# ARE_adaptadora_PIC_8-14pin.net
KiCad netlist of a schematic drawn in EAGLE
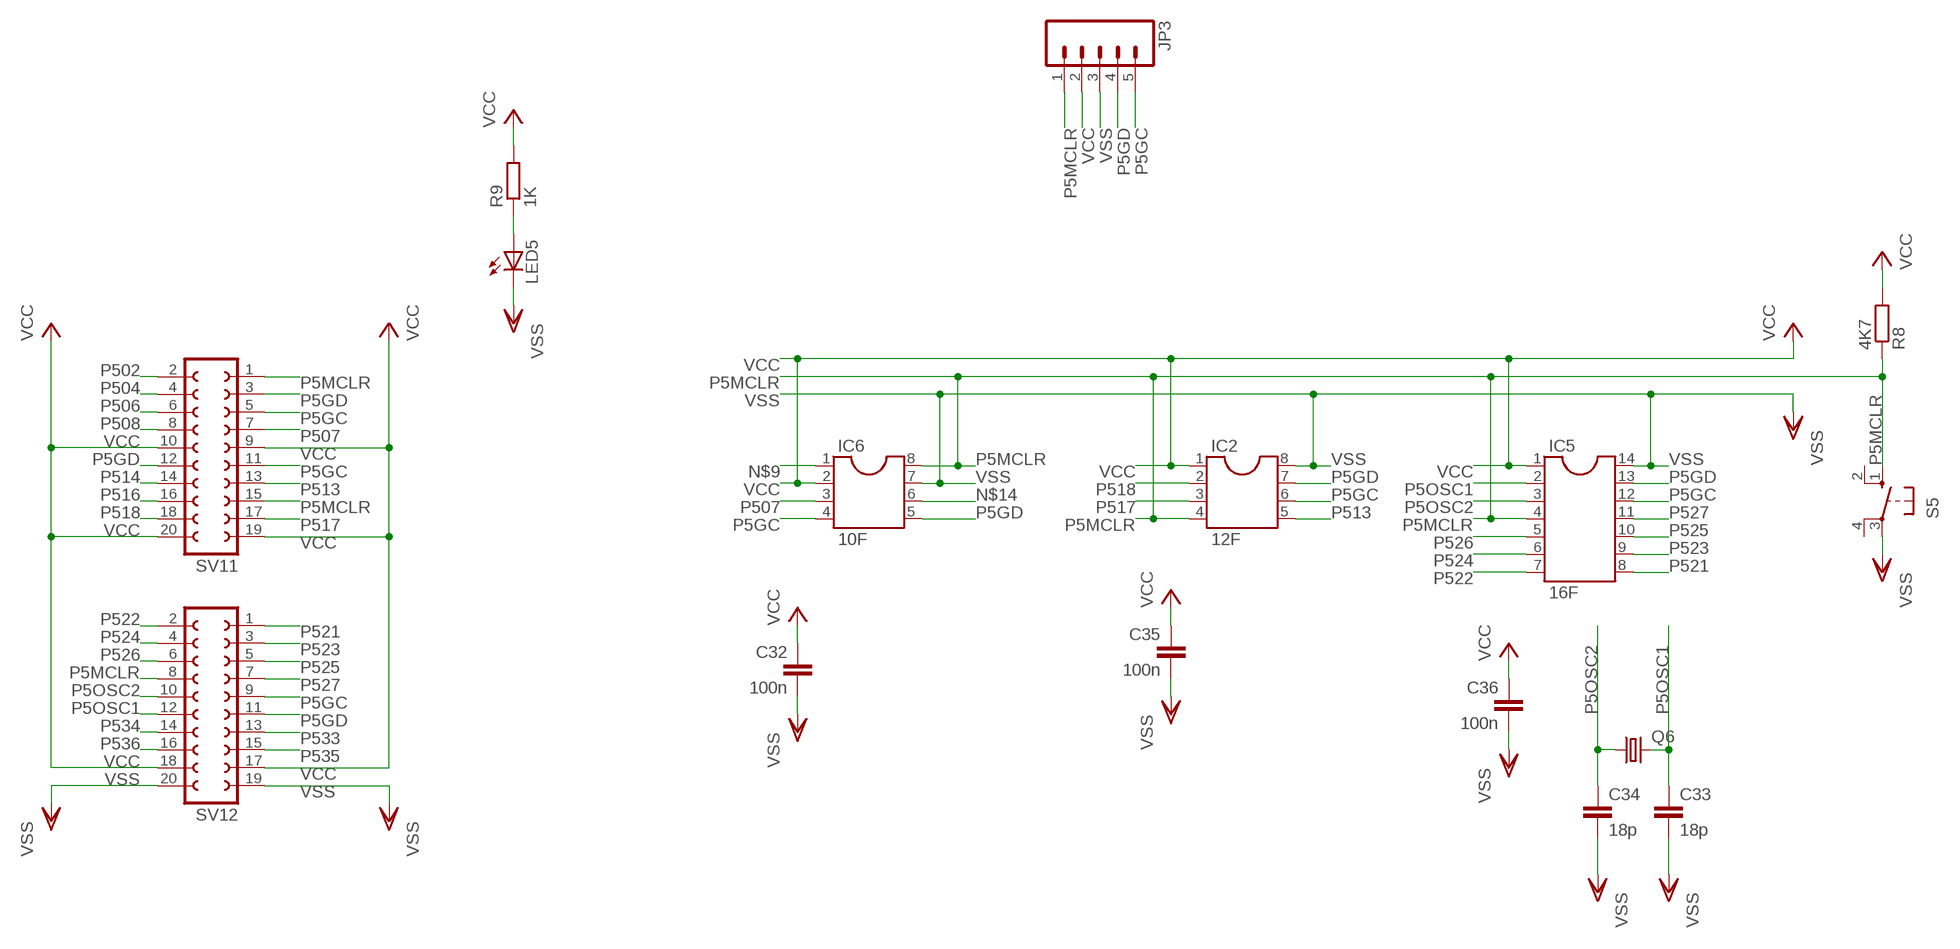
[diagram p0: schematic, sheet 1]

(export (version "E")
  (design (tool "Eeschema 10.0.6"))
  (components
    (comp (ref "C32")
      (value "100n")
      (footprint "eagle-import:C0805")
      (libsource (lib "eagle-import") (part "C-EUC0805"))
    )
    (comp (ref "C33")
      (value "18p")
      (footprint "eagle-import:C0805")
      (libsource (lib "eagle-import") (part "C-EUC0805"))
    )
    (comp (ref "C34")
      (value "18p")
      (footprint "eagle-import:C0805")
      (libsource (lib "eagle-import") (part "C-EUC0805"))
    )
    (comp (ref "C35")
      (value "100n")
      (footprint "eagle-import:C0805")
      (libsource (lib "eagle-import") (part "C-EUC0805"))
    )
    (comp (ref "C36")
      (value "100n")
      (footprint "eagle-import:C0805")
      (libsource (lib "eagle-import") (part "C-EUC0805"))
    )
    (comp (ref "IC2")
      (value "12F")
      (footprint "eagle-import:SOCKET-08")
      (libsource (lib "eagle-import") (part "DIL8S"))
    )
    (comp (ref "IC5")
      (value "16F")
      (footprint "eagle-import:SOCKET-14")
      (libsource (lib "eagle-import") (part "DIL14S"))
    )
    (comp (ref "IC6")
      (value "10F")
      (footprint "eagle-import:SOCKET-08")
      (libsource (lib "eagle-import") (part "DIL8S"))
    )
    (comp (ref "JP3")
      (value "M05PTH")
      (footprint "eagle-import:1X05")
      (libsource (lib "eagle-import") (part "M05PTH"))
    )
    (comp (ref "LED5")
      (value "LEDCHIPLED_0805")
      (footprint "eagle-import:CHIPLED_0805")
      (libsource (lib "eagle-import") (part "LEDCHIPLED_0805"))
    )
    (comp (ref "Q6")
      (value "CRYSTALHC18U-V")
      (footprint "eagle-import:HC18U-V")
      (libsource (lib "eagle-import") (part "CRYSTALHC18U-V"))
    )
    (comp (ref "R8")
      (value "4K7")
      (footprint "eagle-import:R0805")
      (libsource (lib "eagle-import") (part "R-EU_R0805"))
    )
    (comp (ref "R9")
      (value "1K")
      (footprint "eagle-import:R0805")
      (libsource (lib "eagle-import") (part "R-EU_R0805"))
    )
    (comp (ref "S5")
      (value "10-XX")
      (footprint "eagle-import:B3F-10XX")
      (fields
        (field (name "MPN") "B3F-1000")
        (field (name "MPN_1") "B3F-1000")
        (field (name "OC_FARNELL") "176432")
        (field (name "OC_NEWARK") "36M3542")
      )
      (libsource (lib "eagle-import") (part "10-XX"))
    )
    (comp (ref "SV11")
      (value "FE10-2W")
      (footprint "eagle-import:FE10-2W")
      (libsource (lib "eagle-import") (part "FE10-2W"))
    )
    (comp (ref "SV12")
      (value "FE10-2W")
      (footprint "eagle-import:FE10-2W")
      (libsource (lib "eagle-import") (part "FE10-2W"))
    )
  )
  (nets
    (net (code "1") (name "/N$9") (class "Default")
      (node (ref "IC6") (pin "1") (pinfunction "1_1") (pintype "passive"))
    )
    (net (code "2") (name "/N$14") (class "Default")
      (node (ref "IC6") (pin "6") (pinfunction "6_6") (pintype "passive"))
    )
    (net (code "3") (name "/P5GC") (class "Default")
      (node (ref "IC2") (pin "6") (pinfunction "6_6") (pintype "passive"))
      (node (ref "IC5") (pin "12") (pinfunction "12_12") (pintype "passive"))
      (node (ref "IC6") (pin "4") (pinfunction "4_4") (pintype "passive"))
      (node (ref "JP3") (pin "5") (pinfunction "5_5") (pintype "passive"))
      (node (ref "SV11") (pin "11") (pinfunction "11_11") (pintype "passive"))
      (node (ref "SV11") (pin "5") (pinfunction "5_5") (pintype "passive"))
      (node (ref "SV12") (pin "9") (pinfunction "9_9") (pintype "passive"))
    )
    (net (code "4") (name "/P5GD") (class "Default")
      (node (ref "IC2") (pin "7") (pinfunction "7_7") (pintype "passive"))
      (node (ref "IC5") (pin "13") (pinfunction "13_13") (pintype "passive"))
      (node (ref "IC6") (pin "5") (pinfunction "5_5") (pintype "passive"))
      (node (ref "JP3") (pin "4") (pinfunction "4_4") (pintype "passive"))
      (node (ref "SV11") (pin "12") (pinfunction "12_12") (pintype "passive"))
      (node (ref "SV11") (pin "3") (pinfunction "3_3") (pintype "passive"))
      (node (ref "SV12") (pin "11") (pinfunction "11_11") (pintype "passive"))
    )
    (net (code "5") (name "/P5MCLR") (class "Default")
      (node (ref "IC2") (pin "4") (pinfunction "4_4") (pintype "passive"))
      (node (ref "IC5") (pin "4") (pinfunction "4_4") (pintype "passive"))
      (node (ref "IC6") (pin "8") (pinfunction "8_8") (pintype "passive"))
      (node (ref "JP3") (pin "1") (pinfunction "1_1") (pintype "passive"))
      (node (ref "R8") (pin "1") (pinfunction "1_1") (pintype "passive"))
      (node (ref "S5") (pin "1") (pinfunction "S_1") (pintype "passive"))
      (node (ref "SV11") (pin "1") (pinfunction "1_1") (pintype "passive"))
      (node (ref "SV11") (pin "15") (pinfunction "15_15") (pintype "passive"))
      (node (ref "SV12") (pin "8") (pinfunction "8_8") (pintype "passive"))
    )
    (net (code "6") (name "/P5OSC1") (class "Default")
      (node (ref "C33") (pin "1") (pinfunction "1_1") (pintype "passive"))
      (node (ref "IC5") (pin "2") (pinfunction "2_2") (pintype "passive"))
      (node (ref "Q6") (pin "2") (pinfunction "2_2") (pintype "passive"))
      (node (ref "SV12") (pin "12") (pinfunction "12_12") (pintype "passive"))
    )
    (net (code "7") (name "/P5OSC2") (class "Default")
      (node (ref "C34") (pin "1") (pinfunction "1_1") (pintype "passive"))
      (node (ref "IC5") (pin "3") (pinfunction "3_3") (pintype "passive"))
      (node (ref "Q6") (pin "1") (pinfunction "1_1") (pintype "passive"))
      (node (ref "SV12") (pin "10") (pinfunction "10_10") (pintype "passive"))
    )
    (net (code "8") (name "/P502") (class "Default")
      (node (ref "SV11") (pin "2") (pinfunction "2_2") (pintype "passive"))
    )
    (net (code "9") (name "/P504") (class "Default")
      (node (ref "SV11") (pin "4") (pinfunction "4_4") (pintype "passive"))
    )
    (net (code "10") (name "/P506") (class "Default")
      (node (ref "SV11") (pin "6") (pinfunction "6_6") (pintype "passive"))
    )
    (net (code "11") (name "/P507") (class "Default")
      (node (ref "IC6") (pin "3") (pinfunction "3_3") (pintype "passive"))
      (node (ref "SV11") (pin "7") (pinfunction "7_7") (pintype "passive"))
    )
    (net (code "12") (name "/P508") (class "Default")
      (node (ref "SV11") (pin "8") (pinfunction "8_8") (pintype "passive"))
    )
    (net (code "13") (name "/P513") (class "Default")
      (node (ref "IC2") (pin "5") (pinfunction "5_5") (pintype "passive"))
      (node (ref "SV11") (pin "13") (pinfunction "13_13") (pintype "passive"))
    )
    (net (code "14") (name "/P514") (class "Default")
      (node (ref "SV11") (pin "14") (pinfunction "14_14") (pintype "passive"))
    )
    (net (code "15") (name "/P516") (class "Default")
      (node (ref "SV11") (pin "16") (pinfunction "16_16") (pintype "passive"))
    )
    (net (code "16") (name "/P517") (class "Default")
      (node (ref "IC2") (pin "3") (pinfunction "3_3") (pintype "passive"))
      (node (ref "SV11") (pin "17") (pinfunction "17_17") (pintype "passive"))
    )
    (net (code "17") (name "/P518") (class "Default")
      (node (ref "IC2") (pin "2") (pinfunction "2_2") (pintype "passive"))
      (node (ref "SV11") (pin "18") (pinfunction "18_18") (pintype "passive"))
    )
    (net (code "18") (name "/P521") (class "Default")
      (node (ref "IC5") (pin "8") (pinfunction "8_8") (pintype "passive"))
      (node (ref "SV12") (pin "1") (pinfunction "1_1") (pintype "passive"))
    )
    (net (code "19") (name "/P522") (class "Default")
      (node (ref "IC5") (pin "7") (pinfunction "7_7") (pintype "passive"))
      (node (ref "SV12") (pin "2") (pinfunction "2_2") (pintype "passive"))
    )
    (net (code "20") (name "/P523") (class "Default")
      (node (ref "IC5") (pin "9") (pinfunction "9_9") (pintype "passive"))
      (node (ref "SV12") (pin "3") (pinfunction "3_3") (pintype "passive"))
    )
    (net (code "21") (name "/P524") (class "Default")
      (node (ref "IC5") (pin "6") (pinfunction "6_6") (pintype "passive"))
      (node (ref "SV12") (pin "4") (pinfunction "4_4") (pintype "passive"))
    )
    (net (code "22") (name "/P525") (class "Default")
      (node (ref "IC5") (pin "10") (pinfunction "10_10") (pintype "passive"))
      (node (ref "SV12") (pin "5") (pinfunction "5_5") (pintype "passive"))
    )
    (net (code "23") (name "/P526") (class "Default")
      (node (ref "IC5") (pin "5") (pinfunction "5_5") (pintype "passive"))
      (node (ref "SV12") (pin "6") (pinfunction "6_6") (pintype "passive"))
    )
    (net (code "24") (name "/P527") (class "Default")
      (node (ref "IC5") (pin "11") (pinfunction "11_11") (pintype "passive"))
      (node (ref "SV12") (pin "7") (pinfunction "7_7") (pintype "passive"))
    )
    (net (code "25") (name "/P533") (class "Default")
      (node (ref "SV12") (pin "13") (pinfunction "13_13") (pintype "passive"))
    )
    (net (code "26") (name "/P534") (class "Default")
      (node (ref "SV12") (pin "14") (pinfunction "14_14") (pintype "passive"))
    )
    (net (code "27") (name "/P535") (class "Default")
      (node (ref "SV12") (pin "15") (pinfunction "15_15") (pintype "passive"))
    )
    (net (code "28") (name "/P536") (class "Default")
      (node (ref "SV12") (pin "16") (pinfunction "16_16") (pintype "passive"))
    )
    (net (code "29") (name "Net-(LED5-PadA)") (class "Default")
      (node (ref "LED5") (pin "A") (pinfunction "A_A") (pintype "passive"))
      (node (ref "R9") (pin "1") (pinfunction "1_1") (pintype "passive"))
    )
    (net (code "30") (name "VCC") (class "Default")
      (node (ref "C32") (pin "1") (pinfunction "1_1") (pintype "passive"))
      (node (ref "C35") (pin "1") (pinfunction "1_1") (pintype "passive"))
      (node (ref "C36") (pin "1") (pinfunction "1_1") (pintype "passive"))
      (node (ref "IC2") (pin "1") (pinfunction "1_1") (pintype "passive"))
      (node (ref "IC5") (pin "1") (pinfunction "1_1") (pintype "passive"))
      (node (ref "IC6") (pin "2") (pinfunction "2_2") (pintype "passive"))
      (node (ref "JP3") (pin "2") (pinfunction "2_2") (pintype "passive"))
      (node (ref "R8") (pin "2") (pinfunction "2_2") (pintype "passive"))
      (node (ref "R9") (pin "2") (pinfunction "2_2") (pintype "passive"))
      (node (ref "SV11") (pin "10") (pinfunction "10_10") (pintype "passive"))
      (node (ref "SV11") (pin "19") (pinfunction "19_19") (pintype "passive"))
      (node (ref "SV11") (pin "20") (pinfunction "20_20") (pintype "passive"))
      (node (ref "SV11") (pin "9") (pinfunction "9_9") (pintype "passive"))
      (node (ref "SV12") (pin "17") (pinfunction "17_17") (pintype "passive"))
      (node (ref "SV12") (pin "18") (pinfunction "18_18") (pintype "passive"))
    )
    (net (code "31") (name "VSS") (class "Default")
      (node (ref "C32") (pin "2") (pinfunction "2_2") (pintype "passive"))
      (node (ref "C33") (pin "2") (pinfunction "2_2") (pintype "passive"))
      (node (ref "C34") (pin "2") (pinfunction "2_2") (pintype "passive"))
      (node (ref "C35") (pin "2") (pinfunction "2_2") (pintype "passive"))
      (node (ref "C36") (pin "2") (pinfunction "2_2") (pintype "passive"))
      (node (ref "IC2") (pin "8") (pinfunction "8_8") (pintype "passive"))
      (node (ref "IC5") (pin "14") (pinfunction "14_14") (pintype "passive"))
      (node (ref "IC6") (pin "7") (pinfunction "7_7") (pintype "passive"))
      (node (ref "JP3") (pin "3") (pinfunction "3_3") (pintype "passive"))
      (node (ref "LED5") (pin "C") (pinfunction "C_C") (pintype "passive"))
      (node (ref "S5") (pin "3") (pinfunction "P_3") (pintype "passive"))
      (node (ref "SV12") (pin "19") (pinfunction "19_19") (pintype "passive"))
      (node (ref "SV12") (pin "20") (pinfunction "20_20") (pintype "passive"))
    )
    (net (code "32") (name "unconnected-(S5-P1-Pad4)") (class "Default")
      (node (ref "S5") (pin "4") (pinfunction "P1_4") (pintype "passive"))
    )
    (net (code "33") (name "unconnected-(S5-S1-Pad2)") (class "Default")
      (node (ref "S5") (pin "2") (pinfunction "S1_2") (pintype "passive"))
    )
  )
)
